# Max2_PWR_CPU.net
KiCad netlist of a schematic drawn in EAGLE
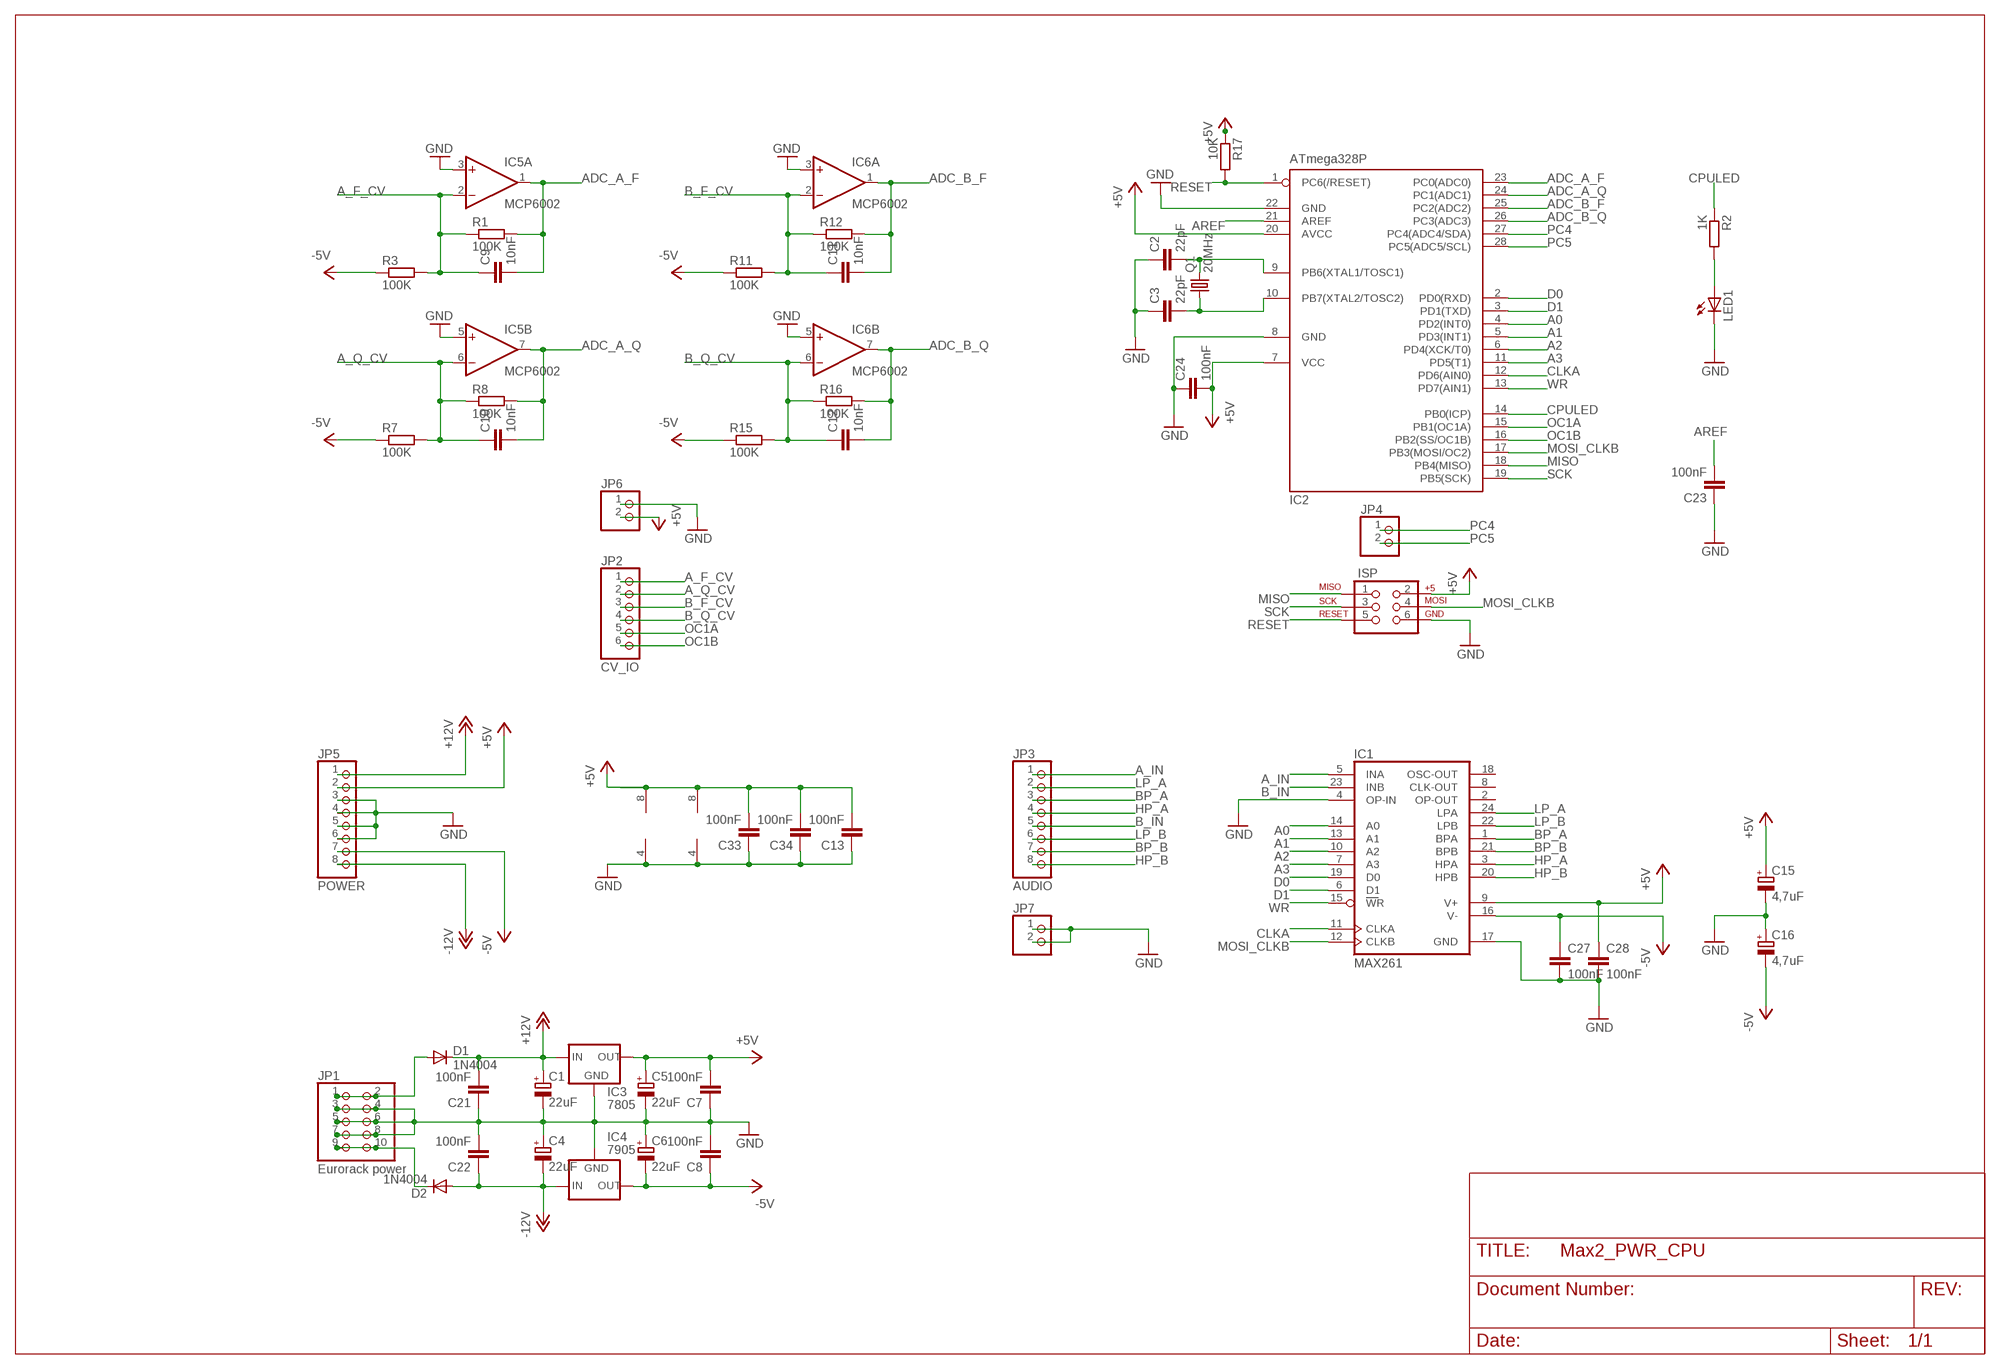
[diagram p0: schematic, sheet 1]

(export (version "E")
  (design (tool "Eeschema 10.0.6"))
  (components
    (comp (ref "C1")
      (value "22uF")
      (footprint "eagle-import:E2,5-7")
      (libsource (lib "eagle-import") (part "CPOL-EUE2.5-7"))
    )
    (comp (ref "C2")
      (value "22pF")
      (footprint "eagle-import:C025-025X050")
      (libsource (lib "eagle-import") (part "C-EU025-025X050"))
    )
    (comp (ref "C3")
      (value "22pF")
      (footprint "eagle-import:C025-025X050")
      (libsource (lib "eagle-import") (part "C-EU025-025X050"))
    )
    (comp (ref "C4")
      (value "22uF")
      (footprint "eagle-import:E2,5-7")
      (libsource (lib "eagle-import") (part "CPOL-EUE2.5-7"))
    )
    (comp (ref "C5")
      (value "22uF")
      (footprint "eagle-import:E2,5-7")
      (libsource (lib "eagle-import") (part "CPOL-EUE2.5-7"))
    )
    (comp (ref "C6")
      (value "22uF")
      (footprint "eagle-import:E2,5-7")
      (libsource (lib "eagle-import") (part "CPOL-EUE2.5-7"))
    )
    (comp (ref "C7")
      (value "100nF")
      (footprint "eagle-import:C025-025X050")
      (libsource (lib "eagle-import") (part "C-EU025-025X050"))
    )
    (comp (ref "C8")
      (value "100nF")
      (footprint "eagle-import:C025-025X050")
      (libsource (lib "eagle-import") (part "C-EU025-025X050"))
    )
    (comp (ref "C9")
      (value "10nF")
      (footprint "eagle-import:C025-025X050")
      (libsource (lib "eagle-import") (part "C-EU025-025X050"))
    )
    (comp (ref "C10")
      (value "10nF")
      (footprint "eagle-import:C025-025X050")
      (libsource (lib "eagle-import") (part "C-EU025-025X050"))
    )
    (comp (ref "C11")
      (value "10nF")
      (footprint "eagle-import:C025-025X050")
      (libsource (lib "eagle-import") (part "C-EU025-025X050"))
    )
    (comp (ref "C12")
      (value "10nF")
      (footprint "eagle-import:C025-025X050")
      (libsource (lib "eagle-import") (part "C-EU025-025X050"))
    )
    (comp (ref "C13")
      (value "100nF")
      (footprint "eagle-import:C025-025X050")
      (libsource (lib "eagle-import") (part "C-EU025-025X050"))
    )
    (comp (ref "C15")
      (value "4,7uF")
      (footprint "eagle-import:E2,5-6")
      (libsource (lib "eagle-import") (part "CPOL-EUE2.5-6"))
    )
    (comp (ref "C16")
      (value "4,7uF")
      (footprint "eagle-import:E2,5-6")
      (libsource (lib "eagle-import") (part "CPOL-EUE2.5-6"))
    )
    (comp (ref "C21")
      (value "100nF")
      (footprint "eagle-import:C025-025X050")
      (libsource (lib "eagle-import") (part "C-EU025-025X050"))
    )
    (comp (ref "C22")
      (value "100nF")
      (footprint "eagle-import:C025-025X050")
      (libsource (lib "eagle-import") (part "C-EU025-025X050"))
    )
    (comp (ref "C23")
      (value "100nF")
      (footprint "eagle-import:C025-025X050")
      (libsource (lib "eagle-import") (part "C-EU025-025X050"))
    )
    (comp (ref "C24")
      (value "100nF")
      (footprint "eagle-import:C025-025X050")
      (libsource (lib "eagle-import") (part "C-EU025-025X050"))
    )
    (comp (ref "C27")
      (value "100nF")
      (footprint "eagle-import:C025-025X050")
      (libsource (lib "eagle-import") (part "C-EU025-025X050"))
    )
    (comp (ref "C28")
      (value "100nF")
      (footprint "eagle-import:C025-025X050")
      (libsource (lib "eagle-import") (part "C-EU025-025X050"))
    )
    (comp (ref "C33")
      (value "100nF")
      (footprint "eagle-import:C025-025X050")
      (libsource (lib "eagle-import") (part "C-EU025-025X050"))
    )
    (comp (ref "C34")
      (value "100nF")
      (footprint "eagle-import:C025-025X050")
      (libsource (lib "eagle-import") (part "C-EU025-025X050"))
    )
    (comp (ref "D1")
      (value "1N4004")
      (footprint "eagle-import:DO41-10")
      (libsource (lib "eagle-import") (part "1N4004"))
    )
    (comp (ref "D2")
      (value "1N4004")
      (footprint "eagle-import:DO41-10")
      (libsource (lib "eagle-import") (part "1N4004"))
    )
    (comp (ref "IC1")
      (value "MAX261")
      (footprint "eagle-import:DIL24-3")
      (fields (field (name "MPN") "MAX261BCNG+"))
      (libsource (lib "eagle-import") (part "MAX261"))
    )
    (comp (ref "IC2")
      (value "ATmega328P")
      (footprint "eagle-import:DIL28-3")
      (libsource (lib "eagle-import") (part "MEGA8-P"))
    )
    (comp (ref "IC3")
      (value "7805")
      (footprint "eagle-import:78XXS")
      (libsource (lib "eagle-import") (part "78XXS"))
    )
    (comp (ref "IC4")
      (value "7905")
      (footprint "eagle-import:79XXS")
      (libsource (lib "eagle-import") (part "79XXS"))
    )
    (comp (ref "IC5")
      (value "MCP6002")
      (footprint "eagle-import:DIL08")
      (libsource (lib "eagle-import") (part "MCP602P"))
    )
    (comp (ref "IC6")
      (value "MCP6002")
      (footprint "eagle-import:DIL08")
      (libsource (lib "eagle-import") (part "MCP602P"))
    )
    (comp (ref "ISP")
      (value "AVR_SPI_PRG_6NS")
      (footprint "eagle-import:2X3-NS")
      (libsource (lib "eagle-import") (part "AVR_SPI_PRG_6NS"))
    )
    (comp (ref "JP1")
      (value "Eurorack power")
      (footprint "eagle-import:2X05")
      (libsource (lib "eagle-import") (part "PINHD-2X5"))
    )
    (comp (ref "JP2")
      (value "CV_IO")
      (footprint "eagle-import:1X06")
      (libsource (lib "eagle-import") (part "PINHD-1X6"))
    )
    (comp (ref "JP3")
      (value "AUDIO")
      (footprint "eagle-import:1X08")
      (libsource (lib "eagle-import") (part "PINHD-1X8"))
    )
    (comp (ref "JP4")
      (value "PINHD-1X2")
      (footprint "eagle-import:1X02")
      (libsource (lib "eagle-import") (part "PINHD-1X2"))
    )
    (comp (ref "JP5")
      (value "POWER")
      (footprint "eagle-import:1X08")
      (libsource (lib "eagle-import") (part "PINHD-1X8"))
    )
    (comp (ref "JP6")
      (value "PINHD-1X2")
      (footprint "eagle-import:1X02")
      (libsource (lib "eagle-import") (part "PINHD-1X2"))
    )
    (comp (ref "JP7")
      (value "PINHD-1X2")
      (footprint "eagle-import:1X02")
      (libsource (lib "eagle-import") (part "PINHD-1X2"))
    )
    (comp (ref "LED1")
      (value "LED3MM")
      (footprint "eagle-import:LED3MM")
      (libsource (lib "eagle-import") (part "LED3MM"))
    )
    (comp (ref "Q1")
      (value "20MHz")
      (footprint "eagle-import:HC49_S")
      (libsource (lib "eagle-import") (part "CRYSTALHC49S"))
    )
    (comp (ref "R1")
      (value "100K")
      (footprint "eagle-import:0207_2V")
      (libsource (lib "eagle-import") (part "R-EU_0207/2V"))
    )
    (comp (ref "R2")
      (value "1K")
      (footprint "eagle-import:0207_2V")
      (libsource (lib "eagle-import") (part "R-EU_0207/2V"))
    )
    (comp (ref "R3")
      (value "100K")
      (footprint "eagle-import:0207_2V")
      (libsource (lib "eagle-import") (part "R-EU_0207/2V"))
    )
    (comp (ref "R7")
      (value "100K")
      (footprint "eagle-import:0207_2V")
      (libsource (lib "eagle-import") (part "R-EU_0207/2V"))
    )
    (comp (ref "R8")
      (value "100K")
      (footprint "eagle-import:0207_2V")
      (libsource (lib "eagle-import") (part "R-EU_0207/2V"))
    )
    (comp (ref "R11")
      (value "100K")
      (footprint "eagle-import:0207_2V")
      (libsource (lib "eagle-import") (part "R-EU_0207/2V"))
    )
    (comp (ref "R12")
      (value "100K")
      (footprint "eagle-import:0207_2V")
      (libsource (lib "eagle-import") (part "R-EU_0207/2V"))
    )
    (comp (ref "R15")
      (value "100K")
      (footprint "eagle-import:0207_2V")
      (libsource (lib "eagle-import") (part "R-EU_0207/2V"))
    )
    (comp (ref "R16")
      (value "100K")
      (footprint "eagle-import:0207_2V")
      (libsource (lib "eagle-import") (part "R-EU_0207/2V"))
    )
    (comp (ref "R17")
      (value "10K")
      (footprint "eagle-import:0207_2V")
      (libsource (lib "eagle-import") (part "R-EU_0207/2V"))
    )
  )
  (nets
    (net (code "1") (name "+5V") (class "Default")
      (node (ref "C13") (pin "2") (pinfunction "2_2") (pintype "passive"))
      (node (ref "C15") (pin "+") (pinfunction "+_+") (pintype "passive"))
      (node (ref "C24") (pin "2") (pinfunction "2_2") (pintype "passive"))
      (node (ref "C28") (pin "1") (pinfunction "1_1") (pintype "passive"))
      (node (ref "C33") (pin "2") (pinfunction "2_2") (pintype "passive"))
      (node (ref "C34") (pin "2") (pinfunction "2_2") (pintype "passive"))
      (node (ref "C5") (pin "+") (pinfunction "+_+") (pintype "passive"))
      (node (ref "C7") (pin "2") (pinfunction "2_2") (pintype "passive"))
      (node (ref "IC1") (pin "9") (pinfunction "V+_9") (pintype "power_in"))
      (node (ref "IC2") (pin "20") (pinfunction "AVCC_20") (pintype "power_in"))
      (node (ref "IC2") (pin "7") (pinfunction "VCC_7") (pintype "power_in"))
      (node (ref "IC3") (pin "OUT") (pinfunction "OUT_OUT") (pintype "passive"))
      (node (ref "IC5") (pin "8") (pinfunction "V+_8") (pintype "power_in"))
      (node (ref "IC6") (pin "8") (pinfunction "V+_8") (pintype "power_in"))
      (node (ref "ISP") (pin "2") (pinfunction "2_2") (pintype "passive"))
      (node (ref "JP5") (pin "2") (pinfunction "2_2") (pintype "passive"))
      (node (ref "JP6") (pin "2") (pinfunction "2_2") (pintype "passive"))
      (node (ref "R17") (pin "1") (pinfunction "1_1") (pintype "passive"))
    )
    (net (code "2") (name "+12V") (class "Default")
      (node (ref "C1") (pin "+") (pinfunction "+_+") (pintype "passive"))
      (node (ref "C21") (pin "2") (pinfunction "2_2") (pintype "passive"))
      (node (ref "D1") (pin "C") (pinfunction "C_C") (pintype "passive"))
      (node (ref "IC3") (pin "IN") (pinfunction "IN_IN") (pintype "input"))
      (node (ref "JP5") (pin "1") (pinfunction "1_1") (pintype "passive"))
    )
    (net (code "3") (name "-5V") (class "Default")
      (node (ref "C16") (pin "-") (pinfunction "-_-") (pintype "passive"))
      (node (ref "C27") (pin "1") (pinfunction "1_1") (pintype "passive"))
      (node (ref "C6") (pin "-") (pinfunction "-_-") (pintype "passive"))
      (node (ref "C8") (pin "1") (pinfunction "1_1") (pintype "passive"))
      (node (ref "IC1") (pin "16") (pinfunction "V-_16") (pintype "power_in"))
      (node (ref "IC4") (pin "OUT") (pinfunction "OUT_OUT") (pintype "passive"))
      (node (ref "JP5") (pin "7") (pinfunction "7_7") (pintype "passive"))
      (node (ref "R11") (pin "1") (pinfunction "1_1") (pintype "passive"))
      (node (ref "R15") (pin "1") (pinfunction "1_1") (pintype "passive"))
      (node (ref "R3") (pin "1") (pinfunction "1_1") (pintype "passive"))
      (node (ref "R7") (pin "1") (pinfunction "1_1") (pintype "passive"))
    )
    (net (code "4") (name "-12V") (class "Default")
      (node (ref "C22") (pin "1") (pinfunction "1_1") (pintype "passive"))
      (node (ref "C4") (pin "-") (pinfunction "-_-") (pintype "passive"))
      (node (ref "D2") (pin "A") (pinfunction "A_A") (pintype "passive"))
      (node (ref "IC4") (pin "IN") (pinfunction "IN_IN") (pintype "input"))
      (node (ref "JP5") (pin "8") (pinfunction "8_8") (pintype "passive"))
    )
    (net (code "5") (name "/A0") (class "Default")
      (node (ref "IC1") (pin "14") (pinfunction "A0_14") (pintype "input"))
      (node (ref "IC2") (pin "4") (pinfunction "PD2(INT0)_4") (pintype "bidirectional"))
    )
    (net (code "6") (name "/A1") (class "Default")
      (node (ref "IC1") (pin "13") (pinfunction "A1_13") (pintype "input"))
      (node (ref "IC2") (pin "5") (pinfunction "PD3(INT1)_5") (pintype "bidirectional"))
    )
    (net (code "7") (name "/A2") (class "Default")
      (node (ref "IC1") (pin "10") (pinfunction "A2_10") (pintype "input"))
      (node (ref "IC2") (pin "6") (pinfunction "PD4(XCK/T0)_6") (pintype "bidirectional"))
    )
    (net (code "8") (name "/A3") (class "Default")
      (node (ref "IC1") (pin "7") (pinfunction "A3_7") (pintype "input"))
      (node (ref "IC2") (pin "11") (pinfunction "PD5(T1)_11") (pintype "bidirectional"))
    )
    (net (code "9") (name "/ADC_A_F") (class "Default")
      (node (ref "C9") (pin "2") (pinfunction "2_2") (pintype "passive"))
      (node (ref "IC2") (pin "23") (pinfunction "PC0(ADC0)_23") (pintype "bidirectional"))
      (node (ref "IC5") (pin "1") (pinfunction "OUT_1") (pintype "output"))
      (node (ref "R1") (pin "2") (pinfunction "2_2") (pintype "passive"))
    )
    (net (code "10") (name "/ADC_A_Q") (class "Default")
      (node (ref "C10") (pin "2") (pinfunction "2_2") (pintype "passive"))
      (node (ref "IC2") (pin "24") (pinfunction "PC1(ADC1)_24") (pintype "bidirectional"))
      (node (ref "IC5") (pin "7") (pinfunction "OUT_7") (pintype "output"))
      (node (ref "R8") (pin "2") (pinfunction "2_2") (pintype "passive"))
    )
    (net (code "11") (name "/ADC_B_F") (class "Default")
      (node (ref "C11") (pin "2") (pinfunction "2_2") (pintype "passive"))
      (node (ref "IC2") (pin "25") (pinfunction "PC2(ADC2)_25") (pintype "bidirectional"))
      (node (ref "IC6") (pin "1") (pinfunction "OUT_1") (pintype "output"))
      (node (ref "R12") (pin "2") (pinfunction "2_2") (pintype "passive"))
    )
    (net (code "12") (name "/ADC_B_Q") (class "Default")
      (node (ref "C12") (pin "2") (pinfunction "2_2") (pintype "passive"))
      (node (ref "IC2") (pin "26") (pinfunction "PC3(ADC3)_26") (pintype "bidirectional"))
      (node (ref "IC6") (pin "7") (pinfunction "OUT_7") (pintype "output"))
      (node (ref "R16") (pin "2") (pinfunction "2_2") (pintype "passive"))
    )
    (net (code "13") (name "/AREF") (class "Default")
      (node (ref "C23") (pin "2") (pinfunction "2_2") (pintype "passive"))
      (node (ref "IC2") (pin "21") (pinfunction "AREF_21") (pintype "passive"))
    )
    (net (code "14") (name "/A_F_CV") (class "Default")
      (node (ref "C9") (pin "1") (pinfunction "1_1") (pintype "passive"))
      (node (ref "IC5") (pin "2") (pinfunction "-IN_2") (pintype "input"))
      (node (ref "JP2") (pin "1") (pinfunction "1_1") (pintype "passive"))
      (node (ref "R1") (pin "1") (pinfunction "1_1") (pintype "passive"))
      (node (ref "R3") (pin "2") (pinfunction "2_2") (pintype "passive"))
    )
    (net (code "15") (name "/A_IN") (class "Default")
      (node (ref "IC1") (pin "5") (pinfunction "INA_5") (pintype "input"))
      (node (ref "JP3") (pin "1") (pinfunction "1_1") (pintype "passive"))
    )
    (net (code "16") (name "/A_Q_CV") (class "Default")
      (node (ref "C10") (pin "1") (pinfunction "1_1") (pintype "passive"))
      (node (ref "IC5") (pin "6") (pinfunction "-IN_6") (pintype "input"))
      (node (ref "JP2") (pin "2") (pinfunction "2_2") (pintype "passive"))
      (node (ref "R7") (pin "2") (pinfunction "2_2") (pintype "passive"))
      (node (ref "R8") (pin "1") (pinfunction "1_1") (pintype "passive"))
    )
    (net (code "17") (name "/BP_A") (class "Default")
      (node (ref "IC1") (pin "1") (pinfunction "BPA_1") (pintype "output"))
      (node (ref "JP3") (pin "3") (pinfunction "3_3") (pintype "passive"))
    )
    (net (code "18") (name "/BP_B") (class "Default")
      (node (ref "IC1") (pin "21") (pinfunction "BPB_21") (pintype "output"))
      (node (ref "JP3") (pin "7") (pinfunction "7_7") (pintype "passive"))
    )
    (net (code "19") (name "/B_F_CV") (class "Default")
      (node (ref "C11") (pin "1") (pinfunction "1_1") (pintype "passive"))
      (node (ref "IC6") (pin "2") (pinfunction "-IN_2") (pintype "input"))
      (node (ref "JP2") (pin "3") (pinfunction "3_3") (pintype "passive"))
      (node (ref "R11") (pin "2") (pinfunction "2_2") (pintype "passive"))
      (node (ref "R12") (pin "1") (pinfunction "1_1") (pintype "passive"))
    )
    (net (code "20") (name "/B_IN") (class "Default")
      (node (ref "IC1") (pin "23") (pinfunction "INB_23") (pintype "input"))
      (node (ref "JP3") (pin "5") (pinfunction "5_5") (pintype "passive"))
    )
    (net (code "21") (name "/B_Q_CV") (class "Default")
      (node (ref "C12") (pin "1") (pinfunction "1_1") (pintype "passive"))
      (node (ref "IC6") (pin "6") (pinfunction "-IN_6") (pintype "input"))
      (node (ref "JP2") (pin "4") (pinfunction "4_4") (pintype "passive"))
      (node (ref "R15") (pin "2") (pinfunction "2_2") (pintype "passive"))
      (node (ref "R16") (pin "1") (pinfunction "1_1") (pintype "passive"))
    )
    (net (code "22") (name "/CLKA") (class "Default")
      (node (ref "IC1") (pin "11") (pinfunction "CLKA_11") (pintype "input"))
      (node (ref "IC2") (pin "12") (pinfunction "PD6(AIN0)_12") (pintype "bidirectional"))
    )
    (net (code "23") (name "/CPULED") (class "Default")
      (node (ref "IC2") (pin "14") (pinfunction "PB0(ICP)_14") (pintype "bidirectional"))
      (node (ref "R2") (pin "1") (pinfunction "1_1") (pintype "passive"))
    )
    (net (code "24") (name "/D0") (class "Default")
      (node (ref "IC1") (pin "19") (pinfunction "D0_19") (pintype "input"))
      (node (ref "IC2") (pin "2") (pinfunction "PD0(RXD)_2") (pintype "bidirectional"))
    )
    (net (code "25") (name "/D1") (class "Default")
      (node (ref "IC1") (pin "6") (pinfunction "D1_6") (pintype "input"))
      (node (ref "IC2") (pin "3") (pinfunction "PD1(TXD)_3") (pintype "bidirectional"))
    )
    (net (code "26") (name "/HP_A") (class "Default")
      (node (ref "IC1") (pin "3") (pinfunction "HPA_3") (pintype "output"))
      (node (ref "JP3") (pin "4") (pinfunction "4_4") (pintype "passive"))
    )
    (net (code "27") (name "/HP_B") (class "Default")
      (node (ref "IC1") (pin "20") (pinfunction "HPB_20") (pintype "output"))
      (node (ref "JP3") (pin "8") (pinfunction "8_8") (pintype "passive"))
    )
    (net (code "28") (name "/LP_A") (class "Default")
      (node (ref "IC1") (pin "24") (pinfunction "LPA_24") (pintype "output"))
      (node (ref "JP3") (pin "2") (pinfunction "2_2") (pintype "passive"))
    )
    (net (code "29") (name "/LP_B") (class "Default")
      (node (ref "IC1") (pin "22") (pinfunction "LPB_22") (pintype "output"))
      (node (ref "JP3") (pin "6") (pinfunction "6_6") (pintype "passive"))
    )
    (net (code "30") (name "/MISO") (class "Default")
      (node (ref "IC2") (pin "18") (pinfunction "PB4(MISO)_18") (pintype "bidirectional"))
      (node (ref "ISP") (pin "1") (pinfunction "1_1") (pintype "passive"))
    )
    (net (code "31") (name "/MOSI_CLKB") (class "Default")
      (node (ref "IC1") (pin "12") (pinfunction "CLKB_12") (pintype "input"))
      (node (ref "IC2") (pin "17") (pinfunction "PB3(MOSI/OC2)_17") (pintype "bidirectional"))
      (node (ref "ISP") (pin "4") (pinfunction "4_4") (pintype "passive"))
    )
    (net (code "32") (name "/OC1A") (class "Default")
      (node (ref "IC2") (pin "15") (pinfunction "PB1(OC1A)_15") (pintype "bidirectional"))
      (node (ref "JP2") (pin "5") (pinfunction "5_5") (pintype "passive"))
    )
    (net (code "33") (name "/OC1B") (class "Default")
      (node (ref "IC2") (pin "16") (pinfunction "PB2(SS/OC1B)_16") (pintype "bidirectional"))
      (node (ref "JP2") (pin "6") (pinfunction "6_6") (pintype "passive"))
    )
    (net (code "34") (name "/PC4") (class "Default")
      (node (ref "IC2") (pin "27") (pinfunction "PC4(ADC4/SDA)_27") (pintype "bidirectional"))
      (node (ref "JP4") (pin "1") (pinfunction "1_1") (pintype "passive"))
    )
    (net (code "35") (name "/PC5") (class "Default")
      (node (ref "IC2") (pin "28") (pinfunction "PC5(ADC5/SCL)_28") (pintype "bidirectional"))
      (node (ref "JP4") (pin "2") (pinfunction "2_2") (pintype "passive"))
    )
    (net (code "36") (name "/RESET") (class "Default")
      (node (ref "IC2") (pin "1") (pinfunction "PC6(/RESET)_1") (pintype "bidirectional"))
      (node (ref "ISP") (pin "5") (pinfunction "5_5") (pintype "passive"))
      (node (ref "R17") (pin "2") (pinfunction "2_2") (pintype "passive"))
    )
    (net (code "37") (name "/SCK") (class "Default")
      (node (ref "IC2") (pin "19") (pinfunction "PB5(SCK)_19") (pintype "bidirectional"))
      (node (ref "ISP") (pin "3") (pinfunction "3_3") (pintype "passive"))
    )
    (net (code "38") (name "/WR") (class "Default")
      (node (ref "IC1") (pin "15") (pinfunction "WR_15") (pintype "input"))
      (node (ref "IC2") (pin "13") (pinfunction "PD7(AIN1)_13") (pintype "bidirectional"))
    )
    (net (code "39") (name "GND") (class "Default")
      (node (ref "C1") (pin "-") (pinfunction "-_-") (pintype "passive"))
      (node (ref "C13") (pin "1") (pinfunction "1_1") (pintype "passive"))
      (node (ref "C15") (pin "-") (pinfunction "-_-") (pintype "passive"))
      (node (ref "C16") (pin "+") (pinfunction "+_+") (pintype "passive"))
      (node (ref "C2") (pin "1") (pinfunction "1_1") (pintype "passive"))
      (node (ref "C21") (pin "1") (pinfunction "1_1") (pintype "passive"))
      (node (ref "C22") (pin "2") (pinfunction "2_2") (pintype "passive"))
      (node (ref "C23") (pin "1") (pinfunction "1_1") (pintype "passive"))
      (node (ref "C24") (pin "1") (pinfunction "1_1") (pintype "passive"))
      (node (ref "C27") (pin "2") (pinfunction "2_2") (pintype "passive"))
      (node (ref "C28") (pin "2") (pinfunction "2_2") (pintype "passive"))
      (node (ref "C3") (pin "1") (pinfunction "1_1") (pintype "passive"))
      (node (ref "C33") (pin "1") (pinfunction "1_1") (pintype "passive"))
      (node (ref "C34") (pin "1") (pinfunction "1_1") (pintype "passive"))
      (node (ref "C4") (pin "+") (pinfunction "+_+") (pintype "passive"))
      (node (ref "C5") (pin "-") (pinfunction "-_-") (pintype "passive"))
      (node (ref "C6") (pin "+") (pinfunction "+_+") (pintype "passive"))
      (node (ref "C7") (pin "1") (pinfunction "1_1") (pintype "passive"))
      (node (ref "C8") (pin "2") (pinfunction "2_2") (pintype "passive"))
      (node (ref "IC1") (pin "17") (pinfunction "GND_17") (pintype "power_in"))
      (node (ref "IC1") (pin "4") (pinfunction "OP-IN_4") (pintype "input"))
      (node (ref "IC2") (pin "22") (pinfunction "GND_22") (pintype "power_in"))
      (node (ref "IC2") (pin "8") (pinfunction "GND_8") (pintype "power_in"))
      (node (ref "IC3") (pin "GND") (pinfunction "GND_GND") (pintype "input"))
      (node (ref "IC4") (pin "GND") (pinfunction "GND_GND") (pintype "input"))
      (node (ref "IC5") (pin "3") (pinfunction "+IN_3") (pintype "input"))
      (node (ref "IC5") (pin "4") (pinfunction "V-_4") (pintype "power_in"))
      (node (ref "IC5") (pin "5") (pinfunction "+IN_5") (pintype "input"))
      (node (ref "IC6") (pin "3") (pinfunction "+IN_3") (pintype "input"))
      (node (ref "IC6") (pin "4") (pinfunction "V-_4") (pintype "power_in"))
      (node (ref "IC6") (pin "5") (pinfunction "+IN_5") (pintype "input"))
      (node (ref "ISP") (pin "6") (pinfunction "6_6") (pintype "passive"))
      (node (ref "JP1") (pin "3") (pinfunction "3_3") (pintype "passive"))
      (node (ref "JP1") (pin "4") (pinfunction "4_4") (pintype "passive"))
      (node (ref "JP1") (pin "5") (pinfunction "5_5") (pintype "passive"))
      (node (ref "JP1") (pin "6") (pinfunction "6_6") (pintype "passive"))
      (node (ref "JP1") (pin "7") (pinfunction "7_7") (pintype "passive"))
      (node (ref "JP1") (pin "8") (pinfunction "8_8") (pintype "passive"))
      (node (ref "JP5") (pin "3") (pinfunction "3_3") (pintype "passive"))
      (node (ref "JP5") (pin "4") (pinfunction "4_4") (pintype "passive"))
      (node (ref "JP5") (pin "5") (pinfunction "5_5") (pintype "passive"))
      (node (ref "JP5") (pin "6") (pinfunction "6_6") (pintype "passive"))
      (node (ref "JP6") (pin "1") (pinfunction "1_1") (pintype "passive"))
      (node (ref "JP7") (pin "1") (pinfunction "1_1") (pintype "passive"))
      (node (ref "JP7") (pin "2") (pinfunction "2_2") (pintype "passive"))
      (node (ref "LED1") (pin "K") (pinfunction "C_K") (pintype "passive"))
    )
    (net (code "40") (name "Net-(D1-PadA)") (class "Default")
      (node (ref "D1") (pin "A") (pinfunction "A_A") (pintype "passive"))
      (node (ref "JP1") (pin "1") (pinfunction "1_1") (pintype "passive"))
      (node (ref "JP1") (pin "2") (pinfunction "2_2") (pintype "passive"))
    )
    (net (code "41") (name "Net-(D2-PadC)") (class "Default")
      (node (ref "D2") (pin "C") (pinfunction "C_C") (pintype "passive"))
      (node (ref "JP1") (pin "10") (pinfunction "10_10") (pintype "passive"))
      (node (ref "JP1") (pin "9") (pinfunction "9_9") (pintype "passive"))
    )
    (net (code "42") (name "Net-(IC2-PB6(XTAL1{slash}TOSC1))") (class "Default")
      (node (ref "C2") (pin "2") (pinfunction "2_2") (pintype "passive"))
      (node (ref "IC2") (pin "9") (pinfunction "PB6(XTAL1/TOSC1)_9") (pintype "bidirectional"))
      (node (ref "Q1") (pin "2") (pinfunction "2_2") (pintype "passive"))
    )
    (net (code "43") (name "Net-(IC2-PB7(XTAL2{slash}TOSC2))") (class "Default")
      (node (ref "C3") (pin "2") (pinfunction "2_2") (pintype "passive"))
      (node (ref "IC2") (pin "10") (pinfunction "PB7(XTAL2/TOSC2)_10") (pintype "bidirectional"))
      (node (ref "Q1") (pin "1") (pinfunction "1_1") (pintype "passive"))
    )
    (net (code "44") (name "Net-(LED1-PadA)") (class "Default")
      (node (ref "LED1") (pin "A") (pinfunction "A_A") (pintype "passive"))
      (node (ref "R2") (pin "2") (pinfunction "2_2") (pintype "passive"))
    )
    (net (code "45") (name "unconnected-(IC1-CLK-OUT-Pad8)") (class "Default")
      (node (ref "IC1") (pin "8") (pinfunction "CLK-OUT_8") (pintype "output"))
    )
    (net (code "46") (name "unconnected-(IC1-OP-OUT-Pad2)") (class "Default")
      (node (ref "IC1") (pin "2") (pinfunction "OP-OUT_2") (pintype "output"))
    )
    (net (code "47") (name "unconnected-(IC1-OSC-OUT-Pad18)") (class "Default")
      (node (ref "IC1") (pin "18") (pinfunction "OSC-OUT_18") (pintype "input"))
    )
  )
)
